# Sheet.net
KiCad netlist of a schematic drawn in Altium Designer
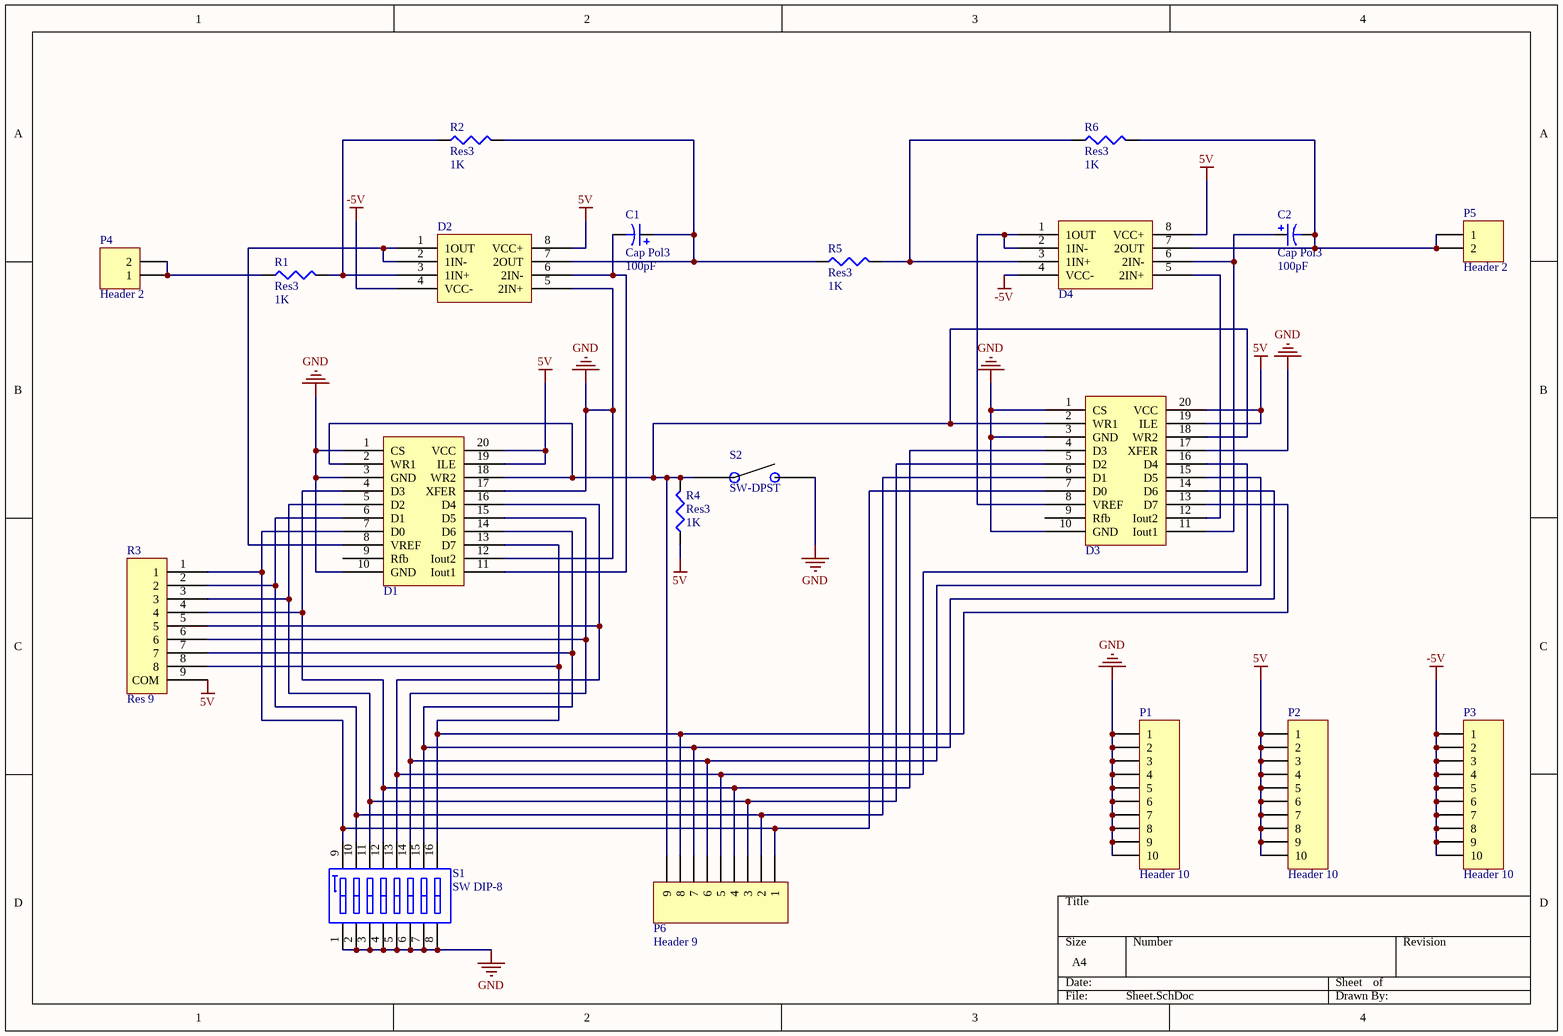
[diagram p0: Sheet.SchDoc]

(export (version "E")
  (design (tool "Eeschema 10.0.6"))
  (components
    (comp (ref "C1")
      (value "Cap Pol3")
      (footprint "1812")
      (description "Polarized Capacitor (Surface Mount)")
      (fields (field (name "ALTIUM_VALUE") "100pF") (field (name "PUBLISHER") "Altium Limited"))
      (libsource (lib "Miscellaneous Devices") (part "Cap Pol3"))
    )
    (comp (ref "C2")
      (value "Cap Pol3")
      (footprint "1812")
      (description "Polarized Capacitor (Surface Mount)")
      (fields (field (name "ALTIUM_VALUE") "100pF") (field (name "PUBLISHER") "Altium Limited"))
      (libsource (lib "Miscellaneous Devices") (part "Cap Pol3"))
    )
    (comp (ref "D1") (value "DAC") (footprint "DIP-20N") (libsource (lib "Schlib") (part "DAC0832")))
    (comp (ref "D2") (value "D") (footprint "DIP-8N") (libsource (lib "Schlib") (part "TL082")))
    (comp (ref "D3") (value "DAC") (footprint "DIP-20N") (libsource (lib "Schlib") (part "DAC0832")))
    (comp (ref "D4") (value "D") (footprint "DIP-8N") (libsource (lib "Schlib") (part "TL082")))
    (comp (ref "P1")
      (value "Header 10")
      (footprint "HDR1X10")
      (description "Header, 10-Pin")
      (fields (field (name "PUBLISHER") "Altium Limited"))
      (libsource (lib "Miscellaneous Connectors") (part "Header 10"))
    )
    (comp (ref "P2")
      (value "Header 10")
      (footprint "HDR1X10")
      (description "Header, 10-Pin")
      (fields (field (name "PUBLISHER") "Altium Limited"))
      (libsource (lib "Miscellaneous Connectors") (part "Header 10"))
    )
    (comp (ref "P3")
      (value "Header 10")
      (footprint "HDR1X10")
      (description "Header, 10-Pin")
      (fields (field (name "PUBLISHER") "Altium Limited"))
      (libsource (lib "Miscellaneous Connectors") (part "Header 10"))
    )
    (comp (ref "P4")
      (value "Header 2")
      (footprint "HDR1X2")
      (description "Header, 2-Pin")
      (fields (field (name "PUBLISHER") "Altium Limited"))
      (libsource (lib "Miscellaneous Connectors") (part "Header 2"))
    )
    (comp (ref "P5")
      (value "Header 2")
      (footprint "HDR1X2")
      (description "Header, 2-Pin")
      (fields (field (name "PUBLISHER") "Altium Limited"))
      (libsource (lib "") (part "Header 2_1"))
    )
    (comp (ref "P6")
      (value "Header 9")
      (footprint "HDR1X9")
      (description "Header, 9-Pin")
      (fields (field (name "PUBLISHER") "Altium Limited"))
      (libsource (lib "Miscellaneous Connectors") (part "Header 9"))
    )
    (comp (ref "R1")
      (value "Res3")
      (footprint "J1-0603")
      (description "Resistor")
      (fields (field (name "ALTIUM_VALUE") "1K") (field (name "PUBLISHER") "Altium Limited"))
      (libsource (lib "Miscellaneous Devices") (part "Res3"))
    )
    (comp (ref "R2")
      (value "Res3")
      (footprint "J1-0603")
      (description "Resistor")
      (fields (field (name "ALTIUM_VALUE") "1K") (field (name "PUBLISHER") "Altium Limited"))
      (libsource (lib "Miscellaneous Devices") (part "Res3"))
    )
    (comp (ref "R3") (value "Res 9") (footprint "HDR1X9") (libsource (lib "Schlib") (part "Res 9")))
    (comp (ref "R4")
      (value "Res3")
      (footprint "J1-0603")
      (description "Resistor")
      (fields (field (name "ALTIUM_VALUE") "1K") (field (name "PUBLISHER") "Altium Limited"))
      (libsource (lib "Miscellaneous Devices") (part "Res3"))
    )
    (comp (ref "R5")
      (value "Res3")
      (footprint "J1-0603")
      (description "Resistor")
      (fields (field (name "ALTIUM_VALUE") "1K") (field (name "PUBLISHER") "Altium Limited"))
      (libsource (lib "Miscellaneous Devices") (part "Res3"))
    )
    (comp (ref "R6")
      (value "Res3")
      (footprint "J1-0603")
      (description "Resistor")
      (fields (field (name "ALTIUM_VALUE") "1K") (field (name "PUBLISHER") "Altium Limited"))
      (libsource (lib "Miscellaneous Devices") (part "Res3"))
    )
    (comp (ref "S1")
      (value "SW DIP-8")
      (footprint "DIP-16")
      (description "DIP Switch, 8 Position, SPST")
      (fields (field (name "PUBLISHER") "Altium Limited"))
      (libsource (lib "Miscellaneous Devices") (part "SW DIP-8"))
    )
    (comp (ref "S2") (value "SW-DPST") (footprint "AN66") (libsource (lib "Schlib") (part "6x6开关")))
  )
  (nets
    (net (code "1") (name "-5V") (class "Default")
      (node (ref "D2") (pin "4") (pinfunction "VCC-_4") (pintype "passive"))
      (node (ref "D4") (pin "4") (pinfunction "VCC-_4") (pintype "passive"))
      (node (ref "P3") (pin "1") (pinfunction "1_1") (pintype "passive"))
      (node (ref "P3") (pin "10") (pinfunction "10_10") (pintype "passive"))
      (node (ref "P3") (pin "2") (pinfunction "2_2") (pintype "passive"))
      (node (ref "P3") (pin "3") (pinfunction "3_3") (pintype "passive"))
      (node (ref "P3") (pin "4") (pinfunction "4_4") (pintype "passive"))
      (node (ref "P3") (pin "5") (pinfunction "5_5") (pintype "passive"))
      (node (ref "P3") (pin "6") (pinfunction "6_6") (pintype "passive"))
      (node (ref "P3") (pin "7") (pinfunction "7_7") (pintype "passive"))
      (node (ref "P3") (pin "8") (pinfunction "8_8") (pintype "passive"))
      (node (ref "P3") (pin "9") (pinfunction "9_9") (pintype "passive"))
    )
    (net (code "2") (name "5V") (class "Default")
      (node (ref "D1") (pin "19") (pinfunction "ILE_19") (pintype "passive"))
      (node (ref "D1") (pin "20") (pinfunction "VCC_20") (pintype "passive"))
      (node (ref "D2") (pin "8") (pinfunction "VCC+_8") (pintype "passive"))
      (node (ref "D3") (pin "19") (pinfunction "ILE_19") (pintype "passive"))
      (node (ref "D3") (pin "20") (pinfunction "VCC_20") (pintype "passive"))
      (node (ref "D4") (pin "8") (pinfunction "VCC+_8") (pintype "passive"))
      (node (ref "P2") (pin "1") (pinfunction "1_1") (pintype "passive"))
      (node (ref "P2") (pin "10") (pinfunction "10_10") (pintype "passive"))
      (node (ref "P2") (pin "2") (pinfunction "2_2") (pintype "passive"))
      (node (ref "P2") (pin "3") (pinfunction "3_3") (pintype "passive"))
      (node (ref "P2") (pin "4") (pinfunction "4_4") (pintype "passive"))
      (node (ref "P2") (pin "5") (pinfunction "5_5") (pintype "passive"))
      (node (ref "P2") (pin "6") (pinfunction "6_6") (pintype "passive"))
      (node (ref "P2") (pin "7") (pinfunction "7_7") (pintype "passive"))
      (node (ref "P2") (pin "8") (pinfunction "8_8") (pintype "passive"))
      (node (ref "P2") (pin "9") (pinfunction "9_9") (pintype "passive"))
      (node (ref "R3") (pin "9") (pinfunction "COM_9") (pintype "passive"))
      (node (ref "R4") (pin "1") (pinfunction "1_1") (pintype "passive"))
    )
    (net (code "3") (name "GND") (class "Default")
      (node (ref "D1") (pin "1") (pinfunction "CS_1") (pintype "passive"))
      (node (ref "D1") (pin "10") (pinfunction "GND_10") (pintype "passive"))
      (node (ref "D1") (pin "12") (pinfunction "Iout2_12") (pintype "passive"))
      (node (ref "D1") (pin "17") (pinfunction "XFER_17") (pintype "passive"))
      (node (ref "D1") (pin "3") (pinfunction "GND_3") (pintype "passive"))
      (node (ref "D2") (pin "5") (pinfunction "2IN+_5") (pintype "passive"))
      (node (ref "D3") (pin "1") (pinfunction "CS_1") (pintype "passive"))
      (node (ref "D3") (pin "10") (pinfunction "GND_10") (pintype "passive"))
      (node (ref "D3") (pin "17") (pinfunction "XFER_17") (pintype "passive"))
      (node (ref "D3") (pin "3") (pinfunction "GND_3") (pintype "passive"))
      (node (ref "P1") (pin "1") (pinfunction "1_1") (pintype "passive"))
      (node (ref "P1") (pin "10") (pinfunction "10_10") (pintype "passive"))
      (node (ref "P1") (pin "2") (pinfunction "2_2") (pintype "passive"))
      (node (ref "P1") (pin "3") (pinfunction "3_3") (pintype "passive"))
      (node (ref "P1") (pin "4") (pinfunction "4_4") (pintype "passive"))
      (node (ref "P1") (pin "5") (pinfunction "5_5") (pintype "passive"))
      (node (ref "P1") (pin "6") (pinfunction "6_6") (pintype "passive"))
      (node (ref "P1") (pin "7") (pinfunction "7_7") (pintype "passive"))
      (node (ref "P1") (pin "8") (pinfunction "8_8") (pintype "passive"))
      (node (ref "P1") (pin "9") (pinfunction "9_9") (pintype "passive"))
      (node (ref "S1") (pin "1") (pinfunction "A1_1") (pintype "passive"))
      (node (ref "S1") (pin "2") (pinfunction "A2_2") (pintype "passive"))
      (node (ref "S1") (pin "3") (pinfunction "A3_3") (pintype "passive"))
      (node (ref "S1") (pin "4") (pinfunction "A4_4") (pintype "passive"))
      (node (ref "S1") (pin "5") (pinfunction "A5_5") (pintype "passive"))
      (node (ref "S1") (pin "6") (pinfunction "A6_6") (pintype "passive"))
      (node (ref "S1") (pin "7") (pinfunction "A7_7") (pintype "passive"))
      (node (ref "S1") (pin "8") (pinfunction "A8_8") (pintype "passive"))
      (node (ref "S2") (pin "1") (pinfunction "1_1") (pintype "passive"))
    )
    (net (code "4") (name "Net-(D1-D0)") (class "Default")
      (node (ref "D1") (pin "7") (pinfunction "D0_7") (pintype "passive"))
      (node (ref "D3") (pin "7") (pinfunction "D0_7") (pintype "passive"))
      (node (ref "P6") (pin "1") (pinfunction "1_1") (pintype "passive"))
      (node (ref "R3") (pin "1") (pinfunction "1_1") (pintype "passive"))
      (node (ref "S1") (pin "9") (pinfunction "B8_9") (pintype "passive"))
    )
    (net (code "5") (name "Net-(D1-D1)") (class "Default")
      (node (ref "D1") (pin "6") (pinfunction "D1_6") (pintype "passive"))
      (node (ref "D3") (pin "6") (pinfunction "D1_6") (pintype "passive"))
      (node (ref "P6") (pin "2") (pinfunction "2_2") (pintype "passive"))
      (node (ref "R3") (pin "2") (pinfunction "2_2") (pintype "passive"))
      (node (ref "S1") (pin "10") (pinfunction "B7_10") (pintype "passive"))
    )
    (net (code "6") (name "Net-(D1-D2)") (class "Default")
      (node (ref "D1") (pin "5") (pinfunction "D2_5") (pintype "passive"))
      (node (ref "D3") (pin "5") (pinfunction "D2_5") (pintype "passive"))
      (node (ref "P6") (pin "3") (pinfunction "3_3") (pintype "passive"))
      (node (ref "R3") (pin "3") (pinfunction "3_3") (pintype "passive"))
      (node (ref "S1") (pin "11") (pinfunction "B6_11") (pintype "passive"))
    )
    (net (code "7") (name "Net-(D1-D3)") (class "Default")
      (node (ref "D1") (pin "4") (pinfunction "D3_4") (pintype "passive"))
      (node (ref "D3") (pin "4") (pinfunction "D3_4") (pintype "passive"))
      (node (ref "P6") (pin "4") (pinfunction "4_4") (pintype "passive"))
      (node (ref "R3") (pin "4") (pinfunction "4_4") (pintype "passive"))
      (node (ref "S1") (pin "12") (pinfunction "B5_12") (pintype "passive"))
    )
    (net (code "8") (name "Net-(D1-D4)") (class "Default")
      (node (ref "D1") (pin "16") (pinfunction "D4_16") (pintype "passive"))
      (node (ref "D3") (pin "16") (pinfunction "D4_16") (pintype "passive"))
      (node (ref "P6") (pin "5") (pinfunction "5_5") (pintype "passive"))
      (node (ref "R3") (pin "5") (pinfunction "5_5") (pintype "passive"))
      (node (ref "S1") (pin "13") (pinfunction "B4_13") (pintype "passive"))
    )
    (net (code "9") (name "Net-(D1-D5)") (class "Default")
      (node (ref "D1") (pin "15") (pinfunction "D5_15") (pintype "passive"))
      (node (ref "D3") (pin "15") (pinfunction "D5_15") (pintype "passive"))
      (node (ref "P6") (pin "6") (pinfunction "6_6") (pintype "passive"))
      (node (ref "R3") (pin "6") (pinfunction "6_6") (pintype "passive"))
      (node (ref "S1") (pin "14") (pinfunction "B3_14") (pintype "passive"))
    )
    (net (code "10") (name "Net-(D1-D6)") (class "Default")
      (node (ref "D1") (pin "14") (pinfunction "D6_14") (pintype "passive"))
      (node (ref "D3") (pin "14") (pinfunction "D6_14") (pintype "passive"))
      (node (ref "P6") (pin "7") (pinfunction "7_7") (pintype "passive"))
      (node (ref "R3") (pin "7") (pinfunction "7_7") (pintype "passive"))
      (node (ref "S1") (pin "15") (pinfunction "B2_15") (pintype "passive"))
    )
    (net (code "11") (name "Net-(D1-D7)") (class "Default")
      (node (ref "D1") (pin "13") (pinfunction "D7_13") (pintype "passive"))
      (node (ref "D3") (pin "13") (pinfunction "D7_13") (pintype "passive"))
      (node (ref "P6") (pin "8") (pinfunction "8_8") (pintype "passive"))
      (node (ref "R3") (pin "8") (pinfunction "8_8") (pintype "passive"))
      (node (ref "S1") (pin "16") (pinfunction "B1_16") (pintype "passive"))
    )
    (net (code "12") (name "Net-(D1-Iout1)") (class "Default")
      (node (ref "C1") (pin "2") (pinfunction "2_2") (pintype "passive"))
      (node (ref "D1") (pin "11") (pinfunction "Iout1_11") (pintype "passive"))
      (node (ref "D2") (pin "6") (pinfunction "2IN-_6") (pintype "passive"))
    )
    (net (code "13") (name "Net-(D1-VREF)") (class "Default")
      (node (ref "D1") (pin "8") (pinfunction "VREF_8") (pintype "passive"))
      (node (ref "D2") (pin "1") (pinfunction "1OUT_1") (pintype "passive"))
      (node (ref "D2") (pin "2") (pinfunction "1IN-_2") (pintype "passive"))
    )
    (net (code "14") (name "Net-(D1-WR1)") (class "Default")
      (node (ref "D1") (pin "18") (pinfunction "WR2_18") (pintype "passive"))
      (node (ref "D1") (pin "2") (pinfunction "WR1_2") (pintype "passive"))
      (node (ref "D3") (pin "18") (pinfunction "WR2_18") (pintype "passive"))
      (node (ref "D3") (pin "2") (pinfunction "WR1_2") (pintype "passive"))
      (node (ref "P6") (pin "9") (pinfunction "9_9") (pintype "passive"))
      (node (ref "R4") (pin "2") (pinfunction "2_2") (pintype "passive"))
      (node (ref "S2") (pin "2") (pinfunction "2_2") (pintype "passive"))
    )
    (net (code "15") (name "Net-(D2-1IN+)") (class "Default")
      (node (ref "D2") (pin "3") (pinfunction "1IN+_3") (pintype "passive"))
      (node (ref "R1") (pin "2") (pinfunction "2_2") (pintype "passive"))
      (node (ref "R2") (pin "1") (pinfunction "1_1") (pintype "passive"))
    )
    (net (code "16") (name "Net-(D2-2OUT)") (class "Default")
      (node (ref "C1") (pin "1") (pinfunction "1_1") (pintype "passive"))
      (node (ref "D2") (pin "7") (pinfunction "2OUT_7") (pintype "passive"))
      (node (ref "R2") (pin "2") (pinfunction "2_2") (pintype "passive"))
      (node (ref "R5") (pin "1") (pinfunction "1_1") (pintype "passive"))
    )
    (net (code "17") (name "Net-(D3-Iout1)") (class "Default")
      (node (ref "C2") (pin "1") (pinfunction "1_1") (pintype "passive"))
      (node (ref "D3") (pin "11") (pinfunction "Iout1_11") (pintype "passive"))
      (node (ref "D4") (pin "6") (pinfunction "2IN-_6") (pintype "passive"))
    )
    (net (code "18") (name "Net-(D3-Iout2)") (class "Default")
      (node (ref "D3") (pin "12") (pinfunction "Iout2_12") (pintype "passive"))
      (node (ref "D4") (pin "5") (pinfunction "2IN+_5") (pintype "passive"))
    )
    (net (code "19") (name "Net-(D3-VREF)") (class "Default")
      (node (ref "D3") (pin "8") (pinfunction "VREF_8") (pintype "passive"))
      (node (ref "D4") (pin "1") (pinfunction "1OUT_1") (pintype "passive"))
      (node (ref "D4") (pin "2") (pinfunction "1IN-_2") (pintype "passive"))
    )
    (net (code "20") (name "Net-(D4-1IN+)") (class "Default")
      (node (ref "D4") (pin "3") (pinfunction "1IN+_3") (pintype "passive"))
      (node (ref "R5") (pin "2") (pinfunction "2_2") (pintype "passive"))
      (node (ref "R6") (pin "1") (pinfunction "1_1") (pintype "passive"))
    )
    (net (code "21") (name "Net-(D4-2OUT)") (class "Default")
      (node (ref "C2") (pin "2") (pinfunction "2_2") (pintype "passive"))
      (node (ref "D4") (pin "7") (pinfunction "2OUT_7") (pintype "passive"))
      (node (ref "P5") (pin "1") (pinfunction "1_1") (pintype "passive"))
      (node (ref "P5") (pin "2") (pinfunction "2_2") (pintype "passive"))
      (node (ref "R6") (pin "2") (pinfunction "2_2") (pintype "passive"))
    )
    (net (code "22") (name "Net-(P4-Pad1)") (class "Default")
      (node (ref "P4") (pin "1") (pinfunction "1_1") (pintype "passive"))
      (node (ref "P4") (pin "2") (pinfunction "2_2") (pintype "passive"))
      (node (ref "R1") (pin "1") (pinfunction "1_1") (pintype "passive"))
    )
    (net (code "23") (name "unconnected-(D1-Rfb-Pad9)") (class "Default")
      (node (ref "D1") (pin "9") (pinfunction "Rfb_9") (pintype "passive"))
    )
    (net (code "24") (name "unconnected-(D3-Rfb-Pad9)") (class "Default")
      (node (ref "D3") (pin "9") (pinfunction "Rfb_9") (pintype "passive"))
    )
  )
)
